# backscatter_tag_v2_pritsinia.net
KiCad netlist of a schematic drawn in EAGLE
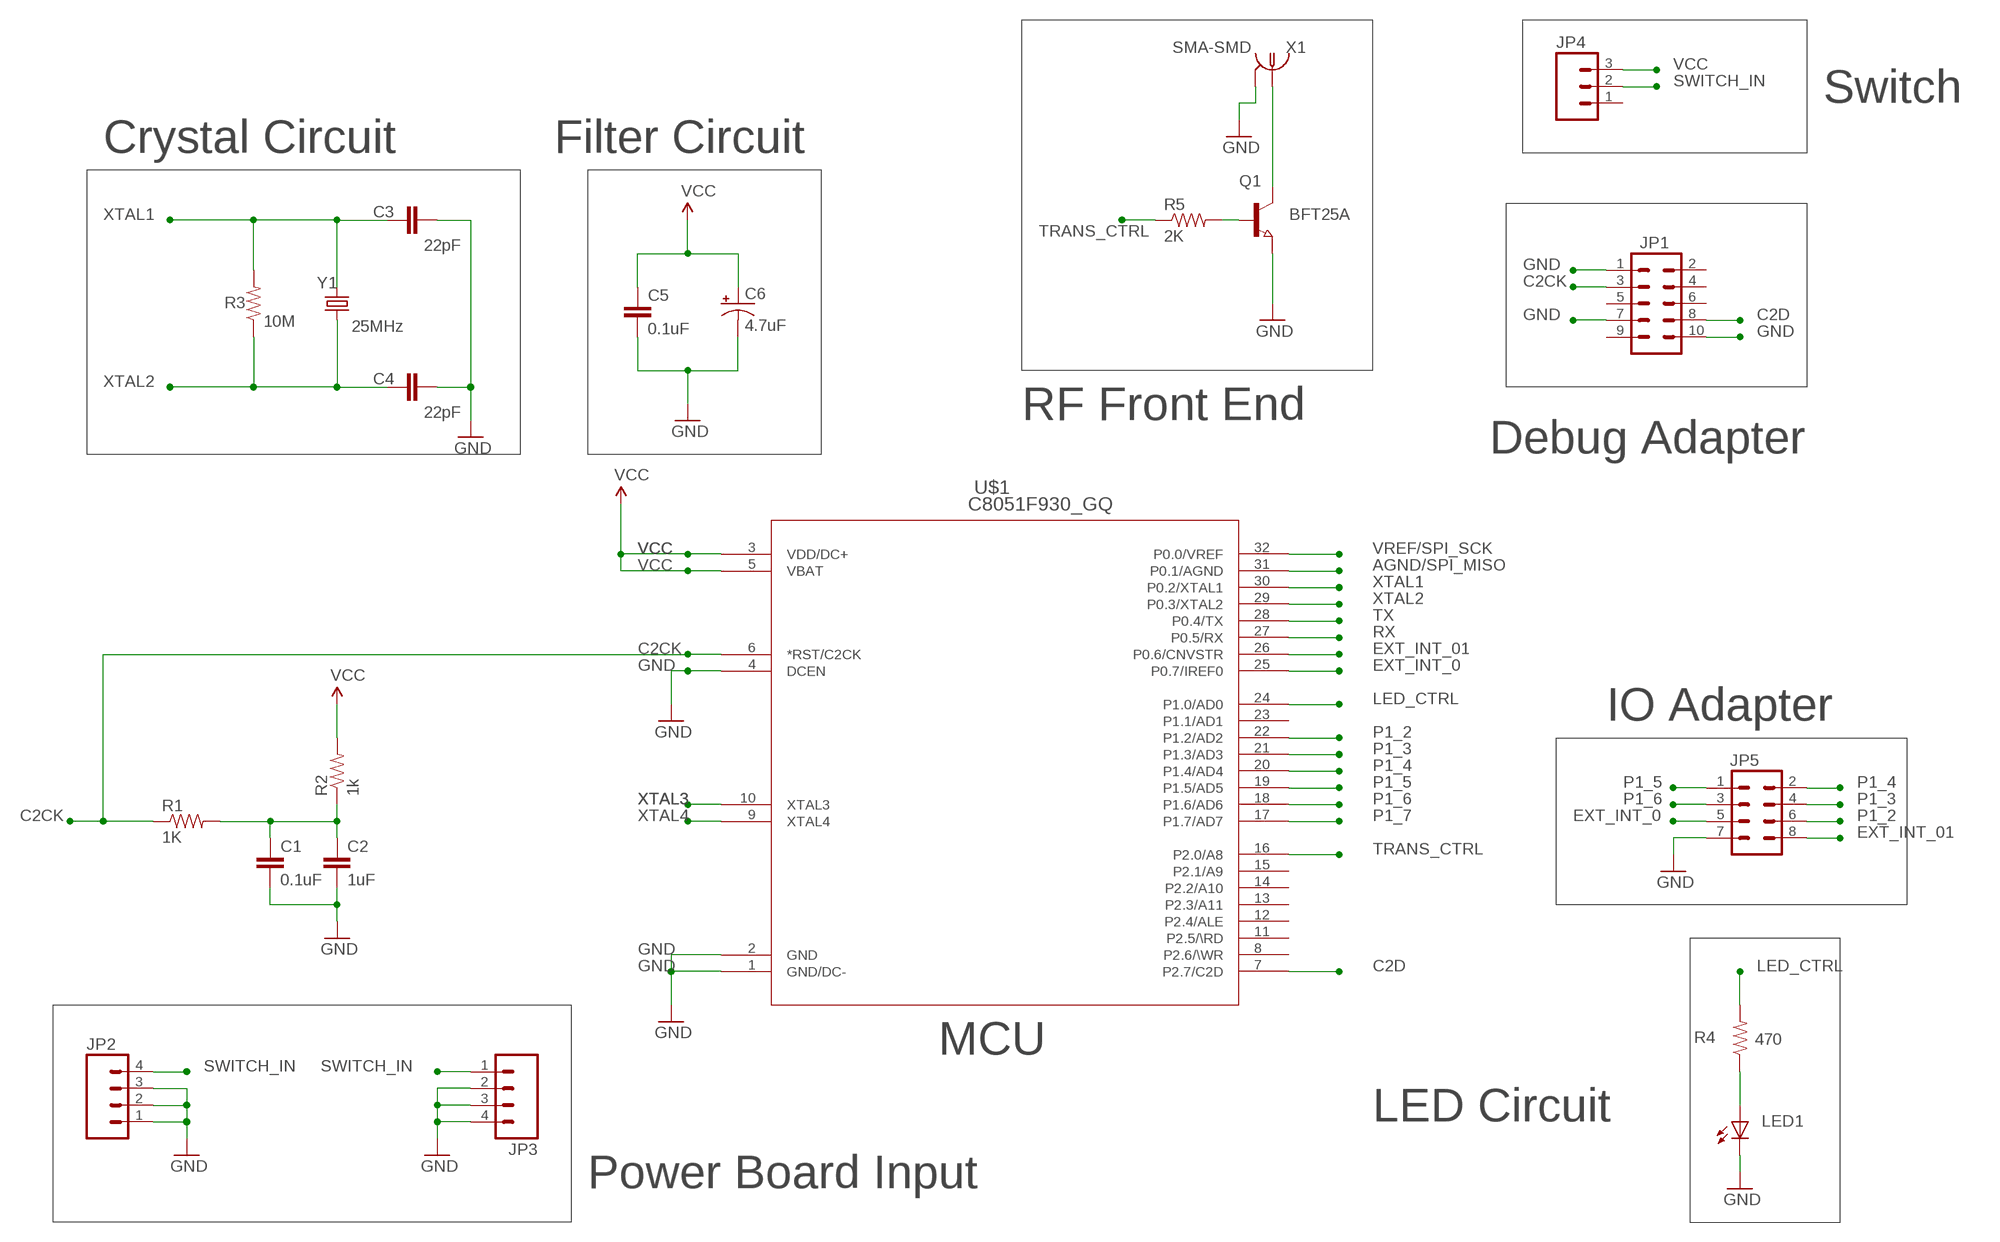
[diagram p0: schematic, sheet 1]

(export (version "E")
  (design (tool "Eeschema 10.0.6"))
  (components
    (comp (ref "C1")
      (value "0.1uF")
      (footprint "eagle-import:0805")
      (libsource (lib "eagle-import") (part "CAP0805"))
    )
    (comp (ref "C2")
      (value "1uF")
      (footprint "eagle-import:0805")
      (libsource (lib "eagle-import") (part "CAP0805"))
    )
    (comp (ref "C3")
      (value "22pF")
      (footprint "eagle-import:0805")
      (libsource (lib "eagle-import") (part "SparkFun-Capacitors_CAP0805"))
    )
    (comp (ref "C4")
      (value "22pF")
      (footprint "eagle-import:0805")
      (libsource (lib "eagle-import") (part "SparkFun-Capacitors_CAP0805"))
    )
    (comp (ref "C5")
      (value "0.1uF")
      (footprint "eagle-import:0805")
      (libsource (lib "eagle-import") (part "SparkFun-Capacitors_CAP0805"))
    )
    (comp (ref "C6")
      (value "4.7uF")
      (footprint "eagle-import:EIA3216")
      (libsource (lib "eagle-import") (part "CAP_POL1206"))
    )
    (comp (ref "JP1")
      (value "M05X2SHD")
      (footprint "eagle-import:2X5-SHROUDED")
      (libsource (lib "eagle-import") (part "M05X2SHD"))
    )
    (comp (ref "JP2")
      (value "M04LOCK")
      (footprint "eagle-import:1X04_LOCK")
      (libsource (lib "eagle-import") (part "M04LOCK"))
    )
    (comp (ref "JP3")
      (value "M04LOCK")
      (footprint "eagle-import:1X04_LOCK")
      (libsource (lib "eagle-import") (part "M04LOCK"))
    )
    (comp (ref "JP4")
      (value "M03LOCK")
      (footprint "eagle-import:1X03_LOCK")
      (libsource (lib "eagle-import") (part "M03LOCK"))
    )
    (comp (ref "JP5")
      (value "M04X2")
      (footprint "eagle-import:2X4")
      (libsource (lib "eagle-import") (part "M04X2"))
    )
    (comp (ref "LED1")
      (value "LED-FKIT-1206")
      (footprint "eagle-import:FKIT-LED-1206")
      (libsource (lib "eagle-import") (part "LED-FKIT-1206"))
    )
    (comp (ref "Q1")
      (value "BFT25A")
      (footprint "eagle-import:SOT23")
      (libsource (lib "eagle-import") (part "NPN-TRANSISTOR_SOT23"))
    )
    (comp (ref "R1")
      (value "1K")
      (footprint "eagle-import:0805")
      (libsource (lib "eagle-import") (part "RESISTOR0805-RES"))
    )
    (comp (ref "R2")
      (value "1k")
      (footprint "eagle-import:0805")
      (libsource (lib "eagle-import") (part "RESISTOR0805-RES"))
    )
    (comp (ref "R3")
      (value "10M")
      (footprint "eagle-import:0805")
      (libsource (lib "eagle-import") (part "SparkFun-Resistors_RESISTOR0805-RES"))
    )
    (comp (ref "R4")
      (value "470")
      (footprint "eagle-import:0805")
      (libsource (lib "eagle-import") (part "SparkFun-Resistors_RESISTOR0805-RES"))
    )
    (comp (ref "R5")
      (value "2K")
      (footprint "eagle-import:0603-RES")
      (libsource (lib "eagle-import") (part "SparkFun-Resistors_RESISTOR0603-RES"))
    )
    (comp (ref "U$1")
      (value "C8051F930_GQ")
      (footprint "eagle-import:QFP32-7X7-0P8MM")
      (libsource (lib "eagle-import") (part "C8051F930_GQ"))
    )
    (comp (ref "X1")
      (value "SMA-SMD")
      (footprint "eagle-import:SMA-SMD")
      (libsource (lib "eagle-import") (part "SMA-SMD"))
    )
    (comp (ref "Y1")
      (value "25MHz")
      (footprint "eagle-import:HC49US")
      (libsource (lib "eagle-import") (part "CRYSTALHC49US"))
    )
  )
  (nets
    (net (code "1") (name "/AGND{slash}SPI_MISO") (class "Default")
      (node (ref "U$1") (pin "31") (pinfunction "P0.1/AGND_31") (pintype "passive"))
    )
    (net (code "2") (name "/C2CK") (class "Default")
      (node (ref "JP1") (pin "3") (pinfunction "3_3") (pintype "passive"))
      (node (ref "R1") (pin "1") (pinfunction "1_1") (pintype "passive"))
      (node (ref "U$1") (pin "6") (pinfunction "*RST/C2CK_6") (pintype "passive"))
    )
    (net (code "3") (name "/C2D") (class "Default")
      (node (ref "JP1") (pin "8") (pinfunction "8_8") (pintype "passive"))
      (node (ref "U$1") (pin "7") (pinfunction "P2.7/C2D_7") (pintype "passive"))
    )
    (net (code "4") (name "/EXT_INT_0") (class "Default")
      (node (ref "JP5") (pin "5") (pinfunction "5_5") (pintype "passive"))
      (node (ref "U$1") (pin "25") (pinfunction "P0.7/IREF0_25") (pintype "passive"))
    )
    (net (code "5") (name "/EXT_INT_01") (class "Default")
      (node (ref "JP5") (pin "8") (pinfunction "8_8") (pintype "passive"))
      (node (ref "U$1") (pin "26") (pinfunction "P0.6/CNVSTR_26") (pintype "passive"))
    )
    (net (code "6") (name "/LED_CTRL") (class "Default")
      (node (ref "R4") (pin "2") (pinfunction "2_2") (pintype "passive"))
      (node (ref "U$1") (pin "24") (pinfunction "P1.0/AD0_24") (pintype "passive"))
    )
    (net (code "7") (name "/P1_2") (class "Default")
      (node (ref "JP5") (pin "6") (pinfunction "6_6") (pintype "passive"))
      (node (ref "U$1") (pin "22") (pinfunction "P1.2/AD2_22") (pintype "passive"))
    )
    (net (code "8") (name "/P1_3") (class "Default")
      (node (ref "JP5") (pin "4") (pinfunction "4_4") (pintype "passive"))
      (node (ref "U$1") (pin "21") (pinfunction "P1.3/AD3_21") (pintype "passive"))
    )
    (net (code "9") (name "/P1_4") (class "Default")
      (node (ref "JP5") (pin "2") (pinfunction "2_2") (pintype "passive"))
      (node (ref "U$1") (pin "20") (pinfunction "P1.4/AD4_20") (pintype "passive"))
    )
    (net (code "10") (name "/P1_5") (class "Default")
      (node (ref "JP5") (pin "1") (pinfunction "1_1") (pintype "passive"))
      (node (ref "U$1") (pin "19") (pinfunction "P1.5/AD5_19") (pintype "passive"))
    )
    (net (code "11") (name "/P1_6") (class "Default")
      (node (ref "JP5") (pin "3") (pinfunction "3_3") (pintype "passive"))
      (node (ref "U$1") (pin "18") (pinfunction "P1.6/AD6_18") (pintype "passive"))
    )
    (net (code "12") (name "/P1_7") (class "Default")
      (node (ref "U$1") (pin "17") (pinfunction "P1.7/AD7_17") (pintype "passive"))
    )
    (net (code "13") (name "/RX") (class "Default")
      (node (ref "U$1") (pin "27") (pinfunction "P0.5/RX_27") (pintype "passive"))
    )
    (net (code "14") (name "/SWITCH_IN") (class "Default")
      (node (ref "JP2") (pin "4") (pinfunction "4_4") (pintype "passive"))
      (node (ref "JP3") (pin "1") (pinfunction "1_1") (pintype "passive"))
      (node (ref "JP4") (pin "2") (pinfunction "2_2") (pintype "passive"))
    )
    (net (code "15") (name "/TRANS_CTRL") (class "Default")
      (node (ref "R5") (pin "1") (pinfunction "1_1") (pintype "passive"))
      (node (ref "U$1") (pin "16") (pinfunction "P2.0/A8_16") (pintype "passive"))
    )
    (net (code "16") (name "/TX") (class "Default")
      (node (ref "U$1") (pin "28") (pinfunction "P0.4/TX_28") (pintype "passive"))
    )
    (net (code "17") (name "/VREF{slash}SPI_SCK") (class "Default")
      (node (ref "U$1") (pin "32") (pinfunction "P0.0/VREF_32") (pintype "passive"))
    )
    (net (code "18") (name "/XTAL1") (class "Default")
      (node (ref "C3") (pin "1") (pinfunction "1_1") (pintype "passive"))
      (node (ref "R3") (pin "2") (pinfunction "2_2") (pintype "passive"))
      (node (ref "U$1") (pin "30") (pinfunction "P0.2/XTAL1_30") (pintype "passive"))
      (node (ref "Y1") (pin "2") (pinfunction "2_2") (pintype "passive"))
    )
    (net (code "19") (name "/XTAL2") (class "Default")
      (node (ref "C4") (pin "1") (pinfunction "1_1") (pintype "passive"))
      (node (ref "R3") (pin "1") (pinfunction "1_1") (pintype "passive"))
      (node (ref "U$1") (pin "29") (pinfunction "P0.3/XTAL2_29") (pintype "passive"))
      (node (ref "Y1") (pin "1") (pinfunction "1_1") (pintype "passive"))
    )
    (net (code "20") (name "/XTAL3") (class "Default")
      (node (ref "U$1") (pin "10") (pinfunction "XTAL3_10") (pintype "passive"))
    )
    (net (code "21") (name "/XTAL4") (class "Default")
      (node (ref "U$1") (pin "9") (pinfunction "XTAL4_9") (pintype "passive"))
    )
    (net (code "22") (name "GND") (class "Default")
      (node (ref "C1") (pin "2") (pinfunction "2_2") (pintype "passive"))
      (node (ref "C2") (pin "2") (pinfunction "2_2") (pintype "passive"))
      (node (ref "C3") (pin "2") (pinfunction "2_2") (pintype "passive"))
      (node (ref "C4") (pin "2") (pinfunction "2_2") (pintype "passive"))
      (node (ref "C5") (pin "2") (pinfunction "2_2") (pintype "passive"))
      (node (ref "C6") (pin "C") (pinfunction "-_C") (pintype "passive"))
      (node (ref "JP1") (pin "1") (pinfunction "1_1") (pintype "passive"))
      (node (ref "JP1") (pin "10") (pinfunction "10_10") (pintype "passive"))
      (node (ref "JP1") (pin "7") (pinfunction "7_7") (pintype "passive"))
      (node (ref "JP2") (pin "1") (pinfunction "1_1") (pintype "passive"))
      (node (ref "JP2") (pin "2") (pinfunction "2_2") (pintype "passive"))
      (node (ref "JP2") (pin "3") (pinfunction "3_3") (pintype "passive"))
      (node (ref "JP3") (pin "2") (pinfunction "2_2") (pintype "passive"))
      (node (ref "JP3") (pin "3") (pinfunction "3_3") (pintype "passive"))
      (node (ref "JP3") (pin "4") (pinfunction "4_4") (pintype "passive"))
      (node (ref "JP5") (pin "7") (pinfunction "7_7") (pintype "passive"))
      (node (ref "LED1") (pin "C") (pinfunction "C_C") (pintype "passive"))
      (node (ref "Q1") (pin "2") (pinfunction "E_2") (pintype "passive"))
      (node (ref "U$1") (pin "1") (pinfunction "GND/DC-_1") (pintype "passive"))
      (node (ref "U$1") (pin "2") (pinfunction "GND_2") (pintype "passive"))
      (node (ref "U$1") (pin "4") (pinfunction "DCEN_4") (pintype "passive"))
      (node (ref "X1") (pin "2@1") (pinfunction "2_2@1") (pintype "passive"))
      (node (ref "X1") (pin "2@2") (pinfunction "2_2@2") (pintype "passive"))
      (node (ref "X1") (pin "2@3") (pinfunction "2_2@3") (pintype "passive"))
      (node (ref "X1") (pin "2@4") (pinfunction "2_2@4") (pintype "passive"))
      (node (ref "X1") (pin "2@5") (pinfunction "2_2@5") (pintype "passive"))
      (node (ref "X1") (pin "2@6") (pinfunction "2_2@6") (pintype "passive"))
    )
    (net (code "23") (name "Net-(C1-Pad1)") (class "Default")
      (node (ref "C1") (pin "1") (pinfunction "1_1") (pintype "passive"))
      (node (ref "C2") (pin "1") (pinfunction "1_1") (pintype "passive"))
      (node (ref "R1") (pin "2") (pinfunction "2_2") (pintype "passive"))
      (node (ref "R2") (pin "1") (pinfunction "1_1") (pintype "passive"))
    )
    (net (code "24") (name "Net-(LED1-PadA)") (class "Default")
      (node (ref "LED1") (pin "A") (pinfunction "A_A") (pintype "passive"))
      (node (ref "R4") (pin "1") (pinfunction "1_1") (pintype "passive"))
    )
    (net (code "25") (name "Net-(Q1-B)") (class "Default")
      (node (ref "Q1") (pin "1") (pinfunction "B_1") (pintype "passive"))
      (node (ref "R5") (pin "2") (pinfunction "2_2") (pintype "passive"))
    )
    (net (code "26") (name "Net-(Q1-C)") (class "Default")
      (node (ref "Q1") (pin "3") (pinfunction "C_3") (pintype "passive"))
      (node (ref "X1") (pin "1") (pinfunction "1_1") (pintype "passive"))
    )
    (net (code "27") (name "VCC") (class "Default")
      (node (ref "C5") (pin "1") (pinfunction "1_1") (pintype "passive"))
      (node (ref "C6") (pin "A") (pinfunction "+_A") (pintype "passive"))
      (node (ref "JP4") (pin "3") (pinfunction "3_3") (pintype "passive"))
      (node (ref "R2") (pin "2") (pinfunction "2_2") (pintype "passive"))
      (node (ref "U$1") (pin "3") (pinfunction "VDD/DC+_3") (pintype "passive"))
      (node (ref "U$1") (pin "5") (pinfunction "VBAT_5") (pintype "passive"))
    )
    (net (code "28") (name "unconnected-(JP1-Pad2)") (class "Default")
      (node (ref "JP1") (pin "2") (pinfunction "2_2") (pintype "passive"))
    )
    (net (code "29") (name "unconnected-(JP1-Pad4)") (class "Default")
      (node (ref "JP1") (pin "4") (pinfunction "4_4") (pintype "passive"))
    )
    (net (code "30") (name "unconnected-(JP1-Pad5)") (class "Default")
      (node (ref "JP1") (pin "5") (pinfunction "5_5") (pintype "passive"))
    )
    (net (code "31") (name "unconnected-(JP1-Pad6)") (class "Default")
      (node (ref "JP1") (pin "6") (pinfunction "6_6") (pintype "passive"))
    )
    (net (code "32") (name "unconnected-(JP1-Pad9)") (class "Default")
      (node (ref "JP1") (pin "9") (pinfunction "9_9") (pintype "passive"))
    )
    (net (code "33") (name "unconnected-(JP4-Pad1)") (class "Default")
      (node (ref "JP4") (pin "1") (pinfunction "1_1") (pintype "passive"))
    )
    (net (code "34") (name "unconnected-(U$1-P1.1{slash}AD1-Pad23)") (class "Default")
      (node (ref "U$1") (pin "23") (pinfunction "P1.1/AD1_23") (pintype "passive"))
    )
    (net (code "35") (name "unconnected-(U$1-P2.1{slash}A9-Pad15)") (class "Default")
      (node (ref "U$1") (pin "15") (pinfunction "P2.1/A9_15") (pintype "passive"))
    )
    (net (code "36") (name "unconnected-(U$1-P2.2{slash}A10-Pad14)") (class "Default")
      (node (ref "U$1") (pin "14") (pinfunction "P2.2/A10_14") (pintype "passive"))
    )
    (net (code "37") (name "unconnected-(U$1-P2.3{slash}A11-Pad13)") (class "Default")
      (node (ref "U$1") (pin "13") (pinfunction "P2.3/A11_13") (pintype "passive"))
    )
    (net (code "38") (name "unconnected-(U$1-P2.4{slash}ALE-Pad12)") (class "Default")
      (node (ref "U$1") (pin "12") (pinfunction "P2.4/ALE_12") (pintype "passive"))
    )
    (net (code "39") (name "unconnected-(U$1-P2.5{slash}\\RD-Pad11)") (class "Default")
      (node (ref "U$1") (pin "11") (pinfunction "P2.5/\\RD_11") (pintype "passive"))
    )
    (net (code "40") (name "unconnected-(U$1-P2.6{slash}\\WR-Pad8)") (class "Default")
      (node (ref "U$1") (pin "8") (pinfunction "P2.6/\\WR_8") (pintype "passive"))
    )
  )
)
